# Wii_U_TS_Breakout.net
KiCad netlist of a schematic drawn in EAGLE
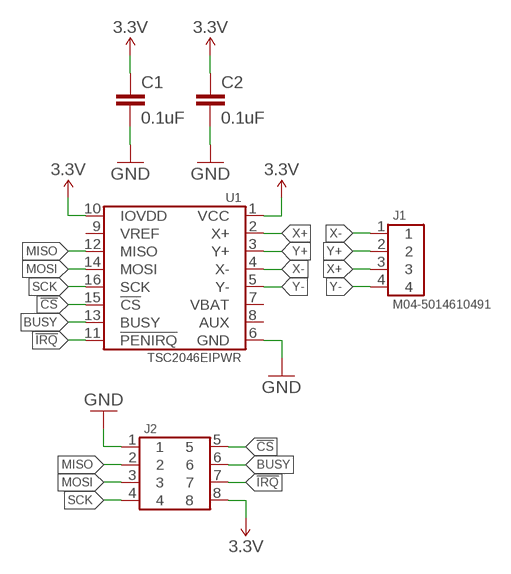
[diagram p0: schematic, sheet 1]

(export (version "E")
  (design (tool "Eeschema 10.0.6"))
  (components
    (comp (ref "C1")
      (value "0.1uF")
      (footprint "eagle-import:0603-CAP")
      (libsource (lib "eagle-import") (part "CAP-0603"))
    )
    (comp (ref "C2")
      (value "0.1uF")
      (footprint "eagle-import:0603-CAP")
      (libsource (lib "eagle-import") (part "CAP-0603"))
    )
    (comp (ref "J1")
      (value "M04-5014610491")
      (footprint "eagle-import:5014610491")
      (libsource (lib "eagle-import") (part "M04-5014610491"))
    )
    (comp (ref "J2")
      (value "M04X2-100MIL")
      (footprint "eagle-import:M04X2-100MIL")
      (libsource (lib "eagle-import") (part "M04X2-100MIL"))
    )
    (comp (ref "U1")
      (value "TSC2046EIPWR")
      (footprint "eagle-import:TSSOP-16")
      (libsource (lib "eagle-import") (part "TSC2046EIPWR"))
    )
  )
  (nets
    (net (code "1") (name "/~{CS}") (class "Default")
      (node (ref "J2") (pin "5") (pinfunction "5_5") (pintype "bidirectional"))
      (node (ref "U1") (pin "15") (pinfunction "~{CS}_15") (pintype "bidirectional"))
    )
    (net (code "2") (name "/~{IRQ}") (class "Default")
      (node (ref "J2") (pin "7") (pinfunction "7_7") (pintype "bidirectional"))
      (node (ref "U1") (pin "11") (pinfunction "~{PENIRQ}_11") (pintype "bidirectional"))
    )
    (net (code "3") (name "3.3V") (class "Default")
      (node (ref "C1") (pin "1") (pinfunction "1_1") (pintype "passive"))
      (node (ref "C2") (pin "1") (pinfunction "1_1") (pintype "passive"))
      (node (ref "J2") (pin "8") (pinfunction "8_8") (pintype "bidirectional"))
      (node (ref "U1") (pin "1") (pinfunction "VCC_1") (pintype "bidirectional"))
      (node (ref "U1") (pin "10") (pinfunction "IOVDD_10") (pintype "bidirectional"))
    )
    (net (code "4") (name "BUSY") (class "Default")
      (node (ref "J2") (pin "6") (pinfunction "6_6") (pintype "bidirectional"))
      (node (ref "U1") (pin "13") (pinfunction "BUSY_13") (pintype "bidirectional"))
    )
    (net (code "5") (name "GND") (class "Default")
      (node (ref "C1") (pin "2") (pinfunction "2_2") (pintype "passive"))
      (node (ref "C2") (pin "2") (pinfunction "2_2") (pintype "passive"))
      (node (ref "J2") (pin "1") (pinfunction "1_1") (pintype "bidirectional"))
      (node (ref "U1") (pin "6") (pinfunction "GND_6") (pintype "bidirectional"))
    )
    (net (code "6") (name "MISO") (class "Default")
      (node (ref "J2") (pin "2") (pinfunction "2_2") (pintype "bidirectional"))
      (node (ref "U1") (pin "12") (pinfunction "MISO_12") (pintype "bidirectional"))
    )
    (net (code "7") (name "MOSI") (class "Default")
      (node (ref "J2") (pin "3") (pinfunction "3_3") (pintype "bidirectional"))
      (node (ref "U1") (pin "14") (pinfunction "MOSI_14") (pintype "bidirectional"))
    )
    (net (code "8") (name "SCK") (class "Default")
      (node (ref "J2") (pin "4") (pinfunction "4_4") (pintype "bidirectional"))
      (node (ref "U1") (pin "16") (pinfunction "SCK_16") (pintype "bidirectional"))
    )
    (net (code "9") (name "X+") (class "Default")
      (node (ref "J1") (pin "3") (pinfunction "3_3") (pintype "bidirectional"))
      (node (ref "U1") (pin "2") (pinfunction "X+_2") (pintype "bidirectional"))
    )
    (net (code "10") (name "X-") (class "Default")
      (node (ref "J1") (pin "1") (pinfunction "1_1") (pintype "bidirectional"))
      (node (ref "U1") (pin "4") (pinfunction "X-_4") (pintype "bidirectional"))
    )
    (net (code "11") (name "Y+") (class "Default")
      (node (ref "J1") (pin "2") (pinfunction "2_2") (pintype "bidirectional"))
      (node (ref "U1") (pin "3") (pinfunction "Y+_3") (pintype "bidirectional"))
    )
    (net (code "12") (name "Y-") (class "Default")
      (node (ref "J1") (pin "4") (pinfunction "4_4") (pintype "bidirectional"))
      (node (ref "U1") (pin "5") (pinfunction "Y-_5") (pintype "bidirectional"))
    )
    (net (code "13") (name "unconnected-(U1-AUX-Pad8)") (class "Default")
      (node (ref "U1") (pin "8") (pinfunction "AUX_8") (pintype "bidirectional"))
    )
    (net (code "14") (name "unconnected-(U1-VBAT-Pad7)") (class "Default")
      (node (ref "U1") (pin "7") (pinfunction "VBAT_7") (pintype "bidirectional"))
    )
    (net (code "15") (name "unconnected-(U1-VREF-Pad9)") (class "Default")
      (node (ref "U1") (pin "9") (pinfunction "VREF_9") (pintype "bidirectional"))
    )
  )
)
